# MSP430F249.net
KiCad netlist of a schematic drawn in Altium Designer
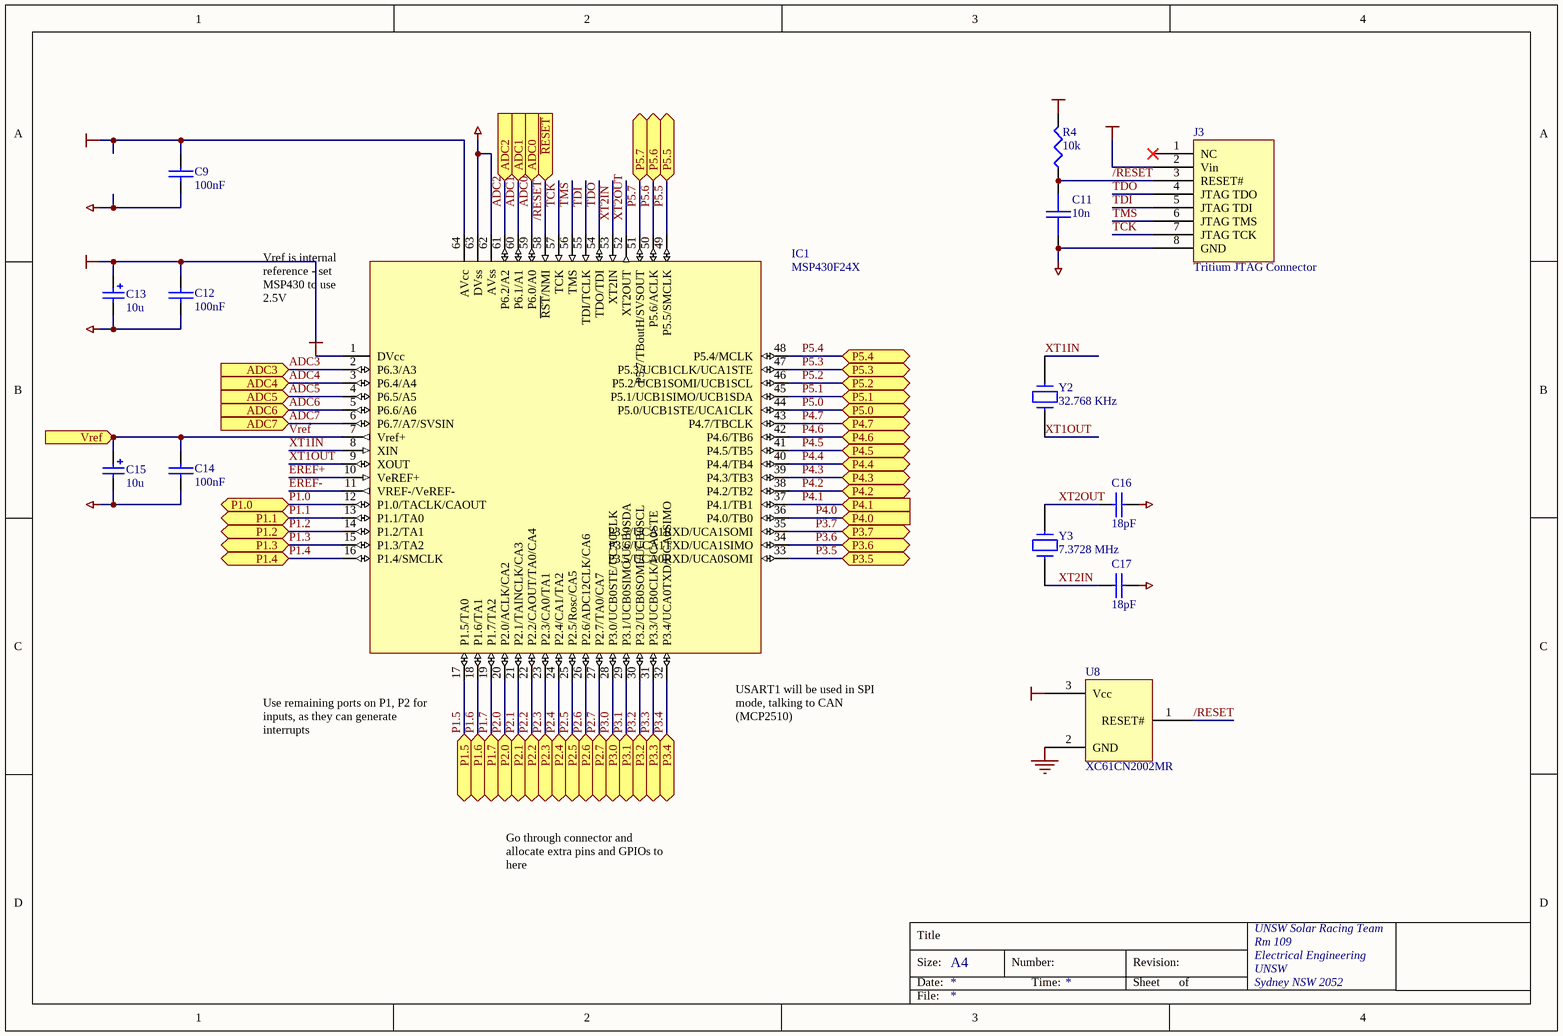
[diagram p0: MSP430F249.SCHDOC]

(export (version "E")
  (design (tool "Eeschema 10.0.6"))
  (components
    (comp (ref "C9")
      (value "100nF")
      (footprint "0603")
      (description "Capacitor")
      (libsource (lib "*") (part "CAP"))
    )
    (comp (ref "C11")
      (value "10n")
      (footprint "0603")
      (description "Capacitor")
      (libsource (lib "SunswiftLib20030312RR") (part "CAP"))
    )
    (comp (ref "C12")
      (value "100nF")
      (footprint "0603")
      (description "Capacitor")
      (libsource (lib "*") (part "CAP"))
    )
    (comp (ref "C13")
      (value "10u")
      (footprint "0805")
      (description "Polarized Capacitor (Surface Mount)")
      (libsource (lib "Miscellaneous Devices") (part "Cap Pol3"))
    )
    (comp (ref "C14")
      (value "100nF")
      (footprint "0603")
      (description "Capacitor")
      (libsource (lib "*") (part "CAP"))
    )
    (comp (ref "C15")
      (value "10u")
      (footprint "0805")
      (description "Polarized Capacitor (Surface Mount)")
      (libsource (lib "Miscellaneous Devices") (part "Cap Pol3"))
    )
    (comp (ref "C16")
      (value "18pF")
      (footprint "0603")
      (description "Capacitor")
      (libsource (lib "*") (part "CAP"))
    )
    (comp (ref "C17")
      (value "18pF")
      (footprint "0603")
      (description "Capacitor")
      (libsource (lib "*") (part "CAP"))
    )
    (comp (ref "IC1") (value "MSP430F24X") (footprint "QFP64") (libsource (lib "MSP430") (part "MSP430F24X")))
    (comp (ref "J3")
      (value "Tritium JTAG Connector")
      (footprint "IDC10")
      (description "Tritium JTAG interface for MSP430")
      (libsource (lib "SunswiftLib20030312RR") (part "430F_JTAG_TRITIUM"))
    )
    (comp (ref "R4")
      (value "10k")
      (footprint "0603")
      (description "Resistor")
      (libsource (lib "SunswiftLib20030312RR") (part "RES1"))
    )
    (comp (ref "U8")
      (value "XC61CN2002MR")
      (footprint "SOT23(3)")
      (description "SOT23 reset generator")
      (libsource (lib "*") (part "XC61F"))
    )
    (comp (ref "Y2")
      (value "32.768 KHz")
      (footprint "WATCHA")
      (description "Crystal")
      (libsource (lib "*") (part "CRYSTAL"))
    )
    (comp (ref "Y3")
      (value "7.3728 MHz")
      (footprint "HC49/4H")
      (description "Crystal")
      (libsource (lib "*") (part "CRYSTAL"))
    )
  )
  (nets
    (net (code "1") (name "/ADC0") (class "Default")
      (node (ref "IC1") (pin "59") (pinfunction "P6.0/A0_59") (pintype "bidirectional"))
    )
    (net (code "2") (name "/ADC1") (class "Default")
      (node (ref "IC1") (pin "60") (pinfunction "P6.1/A1_60") (pintype "bidirectional"))
    )
    (net (code "3") (name "/ADC2") (class "Default")
      (node (ref "IC1") (pin "61") (pinfunction "P6.2/A2_61") (pintype "bidirectional"))
    )
    (net (code "4") (name "/ADC3") (class "Default")
      (node (ref "IC1") (pin "2") (pinfunction "P6.3/A3_2") (pintype "bidirectional"))
    )
    (net (code "5") (name "/ADC4") (class "Default")
      (node (ref "IC1") (pin "3") (pinfunction "P6.4/A4_3") (pintype "bidirectional"))
    )
    (net (code "6") (name "/ADC5") (class "Default")
      (node (ref "IC1") (pin "4") (pinfunction "P6.5/A5_4") (pintype "bidirectional"))
    )
    (net (code "7") (name "/ADC6") (class "Default")
      (node (ref "IC1") (pin "5") (pinfunction "P6.6/A6_5") (pintype "bidirectional"))
    )
    (net (code "8") (name "/ADC7") (class "Default")
      (node (ref "IC1") (pin "6") (pinfunction "P6.7/A7/SVSIN_6") (pintype "bidirectional"))
    )
    (net (code "9") (name "/EREF+") (class "Default")
      (node (ref "IC1") (pin "10") (pinfunction "VeREF+_10") (pintype "input"))
    )
    (net (code "10") (name "/EREF-") (class "Default")
      (node (ref "IC1") (pin "11") (pinfunction "VREF-/VeREF-_11") (pintype "output"))
    )
    (net (code "11") (name "/P1.0") (class "Default")
      (node (ref "IC1") (pin "12") (pinfunction "P1.0/TACLK/CAOUT_12") (pintype "bidirectional"))
    )
    (net (code "12") (name "/P1.1") (class "Default")
      (node (ref "IC1") (pin "13") (pinfunction "P1.1/TA0_13") (pintype "bidirectional"))
    )
    (net (code "13") (name "/P1.2") (class "Default")
      (node (ref "IC1") (pin "14") (pinfunction "P1.2/TA1_14") (pintype "bidirectional"))
    )
    (net (code "14") (name "/P1.3") (class "Default")
      (node (ref "IC1") (pin "15") (pinfunction "P1.3/TA2_15") (pintype "bidirectional"))
    )
    (net (code "15") (name "/P1.4") (class "Default")
      (node (ref "IC1") (pin "16") (pinfunction "P1.4/SMCLK_16") (pintype "bidirectional"))
    )
    (net (code "16") (name "/P1.5") (class "Default")
      (node (ref "IC1") (pin "17") (pinfunction "P1.5/TA0_17") (pintype "bidirectional"))
    )
    (net (code "17") (name "/P1.6") (class "Default")
      (node (ref "IC1") (pin "18") (pinfunction "P1.6/TA1_18") (pintype "bidirectional"))
    )
    (net (code "18") (name "/P1.7") (class "Default")
      (node (ref "IC1") (pin "19") (pinfunction "P1.7/TA2_19") (pintype "bidirectional"))
    )
    (net (code "19") (name "/P2.0") (class "Default")
      (node (ref "IC1") (pin "20") (pinfunction "P2.0/ACLK/CA2_20") (pintype "bidirectional"))
    )
    (net (code "20") (name "/P2.1") (class "Default")
      (node (ref "IC1") (pin "21") (pinfunction "P2.1/TAINCLK/CA3_21") (pintype "bidirectional"))
    )
    (net (code "21") (name "/P2.2") (class "Default")
      (node (ref "IC1") (pin "22") (pinfunction "P2.2/CAOUT/TA0/CA4_22") (pintype "bidirectional"))
    )
    (net (code "22") (name "/P2.3") (class "Default")
      (node (ref "IC1") (pin "23") (pinfunction "P2.3/CA0/TA1_23") (pintype "bidirectional"))
    )
    (net (code "23") (name "/P2.4") (class "Default")
      (node (ref "IC1") (pin "24") (pinfunction "P2.4/CA1/TA2_24") (pintype "bidirectional"))
    )
    (net (code "24") (name "/P2.5") (class "Default")
      (node (ref "IC1") (pin "25") (pinfunction "P2.5/Rosc/CA5_25") (pintype "bidirectional"))
    )
    (net (code "25") (name "/P2.6") (class "Default")
      (node (ref "IC1") (pin "26") (pinfunction "P2.6/ADC12CLK/CA6_26") (pintype "bidirectional"))
    )
    (net (code "26") (name "/P2.7") (class "Default")
      (node (ref "IC1") (pin "27") (pinfunction "P2.7/TA0/CA7_27") (pintype "bidirectional"))
    )
    (net (code "27") (name "/P3.0") (class "Default")
      (node (ref "IC1") (pin "28") (pinfunction "P3.0/UCB0STE/UCA0CLK_28") (pintype "bidirectional"))
    )
    (net (code "28") (name "/P3.1") (class "Default")
      (node (ref "IC1") (pin "29") (pinfunction "P3.1/UCB0SIMO/UCB0SDA_29") (pintype "bidirectional"))
    )
    (net (code "29") (name "/P3.2") (class "Default")
      (node (ref "IC1") (pin "30") (pinfunction "P3.2/UCB0SOMI/UCB0SCL_30") (pintype "bidirectional"))
    )
    (net (code "30") (name "/P3.3") (class "Default")
      (node (ref "IC1") (pin "31") (pinfunction "P3.3/UCB0CLK/UCA0STE_31") (pintype "bidirectional"))
    )
    (net (code "31") (name "/P3.4") (class "Default")
      (node (ref "IC1") (pin "32") (pinfunction "P3.4/UCA0TXD/UCA0SIMO_32") (pintype "bidirectional"))
    )
    (net (code "32") (name "/P3.5") (class "Default")
      (node (ref "IC1") (pin "33") (pinfunction "P3.5/UCA0RXD/UCA0SOMI_33") (pintype "bidirectional"))
    )
    (net (code "33") (name "/P3.6") (class "Default")
      (node (ref "IC1") (pin "34") (pinfunction "P3.6/UCA1TXD/UCA1SIMO_34") (pintype "bidirectional"))
    )
    (net (code "34") (name "/P3.7") (class "Default")
      (node (ref "IC1") (pin "35") (pinfunction "P3.7/UCA1RXD/UCA1SOMI_35") (pintype "bidirectional"))
    )
    (net (code "35") (name "/P4.0") (class "Default")
      (node (ref "IC1") (pin "36") (pinfunction "P4.0/TB0_36") (pintype "bidirectional"))
    )
    (net (code "36") (name "/P4.1") (class "Default")
      (node (ref "IC1") (pin "37") (pinfunction "P4.1/TB1_37") (pintype "bidirectional"))
    )
    (net (code "37") (name "/P4.2") (class "Default")
      (node (ref "IC1") (pin "38") (pinfunction "P4.2/TB2_38") (pintype "bidirectional"))
    )
    (net (code "38") (name "/P4.3") (class "Default")
      (node (ref "IC1") (pin "39") (pinfunction "P4.3/TB3_39") (pintype "bidirectional"))
    )
    (net (code "39") (name "/P4.4") (class "Default")
      (node (ref "IC1") (pin "40") (pinfunction "P4.4/TB4_40") (pintype "bidirectional"))
    )
    (net (code "40") (name "/P4.5") (class "Default")
      (node (ref "IC1") (pin "41") (pinfunction "P4.5/TB5_41") (pintype "bidirectional"))
    )
    (net (code "41") (name "/P4.6") (class "Default")
      (node (ref "IC1") (pin "42") (pinfunction "P4.6/TB6_42") (pintype "bidirectional"))
    )
    (net (code "42") (name "/P4.7") (class "Default")
      (node (ref "IC1") (pin "43") (pinfunction "P4.7/TBCLK_43") (pintype "bidirectional"))
    )
    (net (code "43") (name "/P5.0") (class "Default")
      (node (ref "IC1") (pin "44") (pinfunction "P5.0/UCB1STE/UCA1CLK_44") (pintype "bidirectional"))
    )
    (net (code "44") (name "/P5.1") (class "Default")
      (node (ref "IC1") (pin "45") (pinfunction "P5.1/UCB1SIMO/UCB1SDA_45") (pintype "bidirectional"))
    )
    (net (code "45") (name "/P5.2") (class "Default")
      (node (ref "IC1") (pin "46") (pinfunction "P5.2/UCB1SOMI/UCB1SCL_46") (pintype "bidirectional"))
    )
    (net (code "46") (name "/P5.3") (class "Default")
      (node (ref "IC1") (pin "47") (pinfunction "P5.3/UCB1CLK/UCA1STE_47") (pintype "bidirectional"))
    )
    (net (code "47") (name "/P5.4") (class "Default")
      (node (ref "IC1") (pin "48") (pinfunction "P5.4/MCLK_48") (pintype "bidirectional"))
    )
    (net (code "48") (name "/P5.5") (class "Default")
      (node (ref "IC1") (pin "49") (pinfunction "P5.5/SMCLK_49") (pintype "bidirectional"))
    )
    (net (code "49") (name "/P5.6") (class "Default")
      (node (ref "IC1") (pin "50") (pinfunction "P5.6/ACLK_50") (pintype "bidirectional"))
    )
    (net (code "50") (name "/P5.7") (class "Default")
      (node (ref "IC1") (pin "51") (pinfunction "P5.7/TBoutH/SVSOUT_51") (pintype "bidirectional"))
    )
    (net (code "51") (name "/TCK") (class "Default")
      (node (ref "IC1") (pin "57") (pinfunction "TCK_57") (pintype "input"))
      (node (ref "J3") (pin "7") (pinfunction "JTAG_TCK_7") (pintype "passive"))
    )
    (net (code "52") (name "/TDI") (class "Default")
      (node (ref "IC1") (pin "55") (pinfunction "TDI/TCLK_55") (pintype "input"))
      (node (ref "J3") (pin "5") (pinfunction "JTAG_TDI_5") (pintype "passive"))
    )
    (net (code "53") (name "/TDO") (class "Default")
      (node (ref "IC1") (pin "54") (pinfunction "TDO/TDI_54") (pintype "bidirectional"))
      (node (ref "J3") (pin "4") (pinfunction "JTAG_TDO_4") (pintype "passive"))
    )
    (net (code "54") (name "/TMS") (class "Default")
      (node (ref "IC1") (pin "56") (pinfunction "TMS_56") (pintype "input"))
      (node (ref "J3") (pin "6") (pinfunction "JTAG_TMS_6") (pintype "passive"))
    )
    (net (code "55") (name "/Vref") (class "Default")
      (node (ref "C14") (pin "1") (pinfunction "1_1") (pintype "passive"))
      (node (ref "C15") (pin "1") (pinfunction "1_1") (pintype "passive"))
      (node (ref "IC1") (pin "7") (pinfunction "Vref+_7") (pintype "output"))
    )
    (net (code "56") (name "/XT1IN") (class "Default")
      (node (ref "IC1") (pin "8") (pinfunction "XIN_8") (pintype "input"))
      (node (ref "Y2") (pin "1") (pinfunction "1_1") (pintype "passive"))
    )
    (net (code "57") (name "/XT1OUT") (class "Default")
      (node (ref "IC1") (pin "9") (pinfunction "XOUT_9") (pintype "bidirectional"))
      (node (ref "Y2") (pin "2") (pinfunction "2_2") (pintype "passive"))
    )
    (net (code "58") (name "/XT2IN") (class "Default")
      (node (ref "C17") (pin "1") (pinfunction "1_1") (pintype "passive"))
      (node (ref "IC1") (pin "53") (pinfunction "XT2IN_53") (pintype "input"))
      (node (ref "Y3") (pin "1") (pinfunction "1_1") (pintype "passive"))
    )
    (net (code "59") (name "/XT2OUT") (class "Default")
      (node (ref "C16") (pin "1") (pinfunction "1_1") (pintype "passive"))
      (node (ref "IC1") (pin "52") (pinfunction "XT2OUT_52") (pintype "output"))
      (node (ref "Y3") (pin "2") (pinfunction "2_2") (pintype "passive"))
    )
    (net (code "60") (name "/{slash}RESET") (class "Default")
      (node (ref "C11") (pin "1") (pinfunction "1_1") (pintype "passive"))
      (node (ref "IC1") (pin "58") (pinfunction "~{RST}/NMI_58") (pintype "input"))
      (node (ref "J3") (pin "3") (pinfunction "RESET#_3") (pintype "passive"))
      (node (ref "R4") (pin "1") (pinfunction "1_1") (pintype "passive"))
      (node (ref "U8") (pin "1") (pinfunction "RESET#_1") (pintype "passive"))
    )
    (net (code "61") (name "3V3") (class "Default")
      (node (ref "C12") (pin "1") (pinfunction "1_1") (pintype "passive"))
      (node (ref "C13") (pin "1") (pinfunction "1_1") (pintype "passive"))
      (node (ref "C9") (pin "1") (pinfunction "1_1") (pintype "passive"))
      (node (ref "IC1") (pin "1") (pinfunction "DVcc_1") (pintype "power_in"))
      (node (ref "IC1") (pin "64") (pinfunction "AVcc_64") (pintype "power_in"))
      (node (ref "J3") (pin "2") (pinfunction "Vin_2") (pintype "passive"))
      (node (ref "R4") (pin "2") (pinfunction "2_2") (pintype "passive"))
      (node (ref "U8") (pin "3") (pinfunction "Vcc_3") (pintype "passive"))
    )
    (net (code "62") (name "GND") (class "Default")
      (node (ref "C11") (pin "2") (pinfunction "2_2") (pintype "passive"))
      (node (ref "C12") (pin "2") (pinfunction "2_2") (pintype "passive"))
      (node (ref "C13") (pin "2") (pinfunction "2_2") (pintype "passive"))
      (node (ref "C14") (pin "2") (pinfunction "2_2") (pintype "passive"))
      (node (ref "C15") (pin "2") (pinfunction "2_2") (pintype "passive"))
      (node (ref "C16") (pin "2") (pinfunction "2_2") (pintype "passive"))
      (node (ref "C17") (pin "2") (pinfunction "2_2") (pintype "passive"))
      (node (ref "C9") (pin "2") (pinfunction "2_2") (pintype "passive"))
      (node (ref "IC1") (pin "62") (pinfunction "AVss_62") (pintype "power_in"))
      (node (ref "IC1") (pin "63") (pinfunction "DVss_63") (pintype "power_in"))
      (node (ref "J3") (pin "8") (pinfunction "GND_8") (pintype "passive"))
      (node (ref "U8") (pin "2") (pinfunction "GND_2") (pintype "passive"))
    )
    (net (code "63") (name "unconnected-(J3-NC-Pad1)") (class "Default")
      (node (ref "J3") (pin "1") (pinfunction "NC_1") (pintype "passive+no_connect"))
    )
  )
)
